# Sheet1.net
KiCad netlist of a schematic drawn in Altium Designer
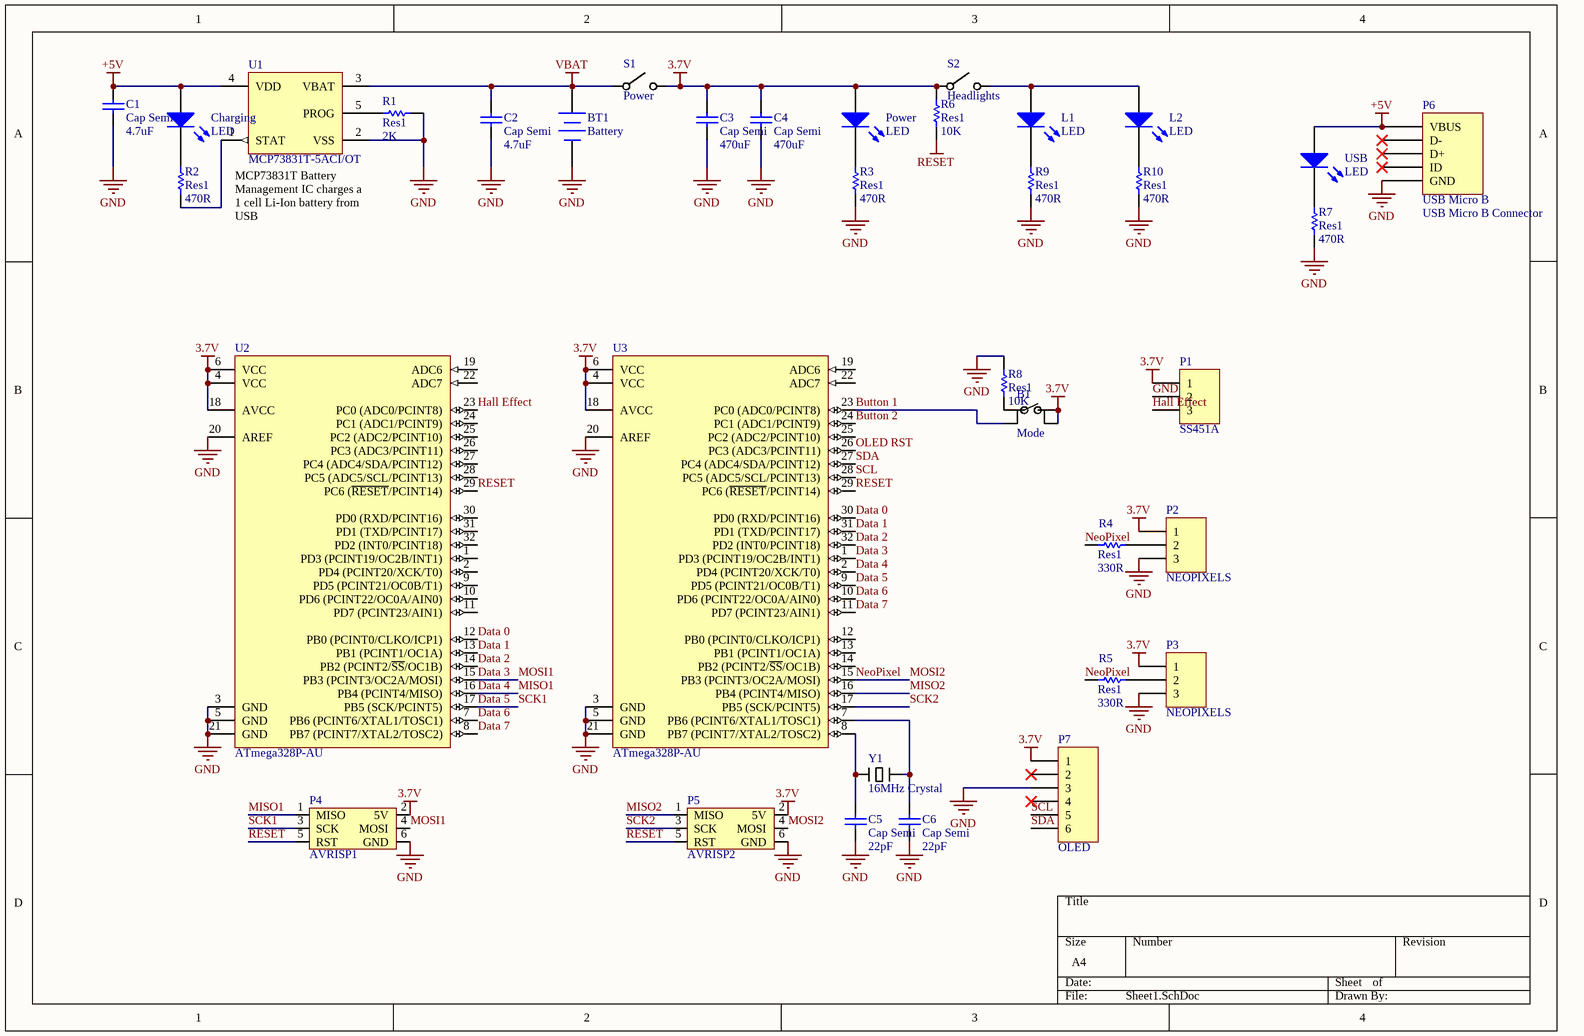
[diagram p0: Sheet1.SchDoc]

(export (version "E")
  (design (tool "Eeschema 10.0.6"))
  (components
    (comp (ref "B1")
      (value "Mode")
      (footprint "SPST-NO")
      (libsource (lib "WillsSchematicLibrary") (part "Switch"))
    )
    (comp (ref "BT1")
      (value "Battery")
      (footprint "BAT-2")
      (description "Multicell Battery")
      (fields (field (name "PUBLISHER") "Altium Limited"))
      (libsource (lib "Miscellaneous Devices") (part "Battery"))
    )
    (comp (ref "C1")
      (value "Cap Semi")
      (footprint "1608[0603]")
      (description "Capacitor (Semiconductor SIM Model)")
      (fields (field (name "ALTIUM_VALUE") "4.7uF") (field (name "PUBLISHER") "Altium Limited"))
      (libsource (lib "Miscellaneous Devices") (part "Cap Semi"))
    )
    (comp (ref "C2")
      (value "Cap Semi")
      (footprint "1608[0603]")
      (description "Capacitor (Semiconductor SIM Model)")
      (fields (field (name "ALTIUM_VALUE") "4.7uF") (field (name "PUBLISHER") "Altium Limited"))
      (libsource (lib "Miscellaneous Devices") (part "Cap Semi"))
    )
    (comp (ref "C3")
      (value "Cap Semi")
      (footprint "CAPAE9983X105M")
      (description "Capacitor (Semiconductor SIM Model)")
      (fields (field (name "ALTIUM_VALUE") "470uF") (field (name "PUBLISHER") "Altium Limited"))
      (libsource (lib "Miscellaneous Devices") (part "Cap Semi"))
    )
    (comp (ref "C4")
      (value "Cap Semi")
      (footprint "CAPAE9983X105M")
      (description "Capacitor (Semiconductor SIM Model)")
      (fields (field (name "ALTIUM_VALUE") "470uF") (field (name "PUBLISHER") "Altium Limited"))
      (libsource (lib "Miscellaneous Devices") (part "Cap Semi"))
    )
    (comp (ref "C5")
      (value "Cap Semi")
      (footprint "1608[0603]")
      (description "Capacitor (Semiconductor SIM Model)")
      (fields (field (name "ALTIUM_VALUE") "22pF") (field (name "PUBLISHER") "Altium Limited"))
      (libsource (lib "Miscellaneous Devices") (part "Cap Semi"))
    )
    (comp (ref "C6")
      (value "Cap Semi")
      (footprint "1608[0603]")
      (description "Capacitor (Semiconductor SIM Model)")
      (fields (field (name "ALTIUM_VALUE") "22pF") (field (name "PUBLISHER") "Altium Limited"))
      (libsource (lib "Miscellaneous Devices") (part "Cap Semi"))
    )
    (comp (ref "Charging")
      (value "LED")
      (footprint "LED0603")
      (description "Typical BLUE SiC LED")
      (fields (field (name "PUBLISHER") "Altium Limited"))
      (libsource (lib "Miscellaneous Devices") (part "LED3"))
    )
    (comp (ref "L1")
      (value "LED")
      (footprint "HDR1X2")
      (description "Typical BLUE SiC LED")
      (fields (field (name "PUBLISHER") "Altium Limited"))
      (libsource (lib "Miscellaneous Devices") (part "LED3"))
    )
    (comp (ref "L2")
      (value "LED")
      (footprint "HDR1X2")
      (description "Typical BLUE SiC LED")
      (fields (field (name "PUBLISHER") "Altium Limited"))
      (libsource (lib "Miscellaneous Devices") (part "LED3"))
    )
    (comp (ref "P1")
      (value "SS451A")
      (footprint "HDR1X3")
      (description "Header, 3-Pin")
      (fields (field (name "PUBLISHER") "Altium Limited"))
      (libsource (lib "Miscellaneous Connectors") (part "Header 3"))
    )
    (comp (ref "P2")
      (value "NEOPIXELS")
      (footprint "HDR1X3")
      (description "Header, 3-Pin")
      (fields (field (name "PUBLISHER") "Altium Limited"))
      (libsource (lib "Miscellaneous Connectors") (part "Header 3"))
    )
    (comp (ref "P3")
      (value "NEOPIXELS")
      (footprint "HDR1X3")
      (description "Header, 3-Pin")
      (fields (field (name "PUBLISHER") "Altium Limited"))
      (libsource (lib "Miscellaneous Connectors") (part "Header 3"))
    )
    (comp (ref "P4")
      (value "AVRISP1")
      (footprint "HDR2X3")
      (libsource (lib "WillsSchematicLibrary") (part "AVRISP"))
    )
    (comp (ref "P5")
      (value "AVRISP2")
      (footprint "HDR2X3")
      (libsource (lib "WillsSchematicLibrary") (part "AVRISP"))
    )
    (comp (ref "P6")
      (value "USB Micro B Connector")
      (footprint "USB Micro B Connector")
      (libsource (lib "WillsSchematicLibrary") (part "USB Micro B Connector"))
    )
    (comp (ref "P7")
      (value "OLED")
      (footprint "HDR1X6")
      (description "Header, 6-Pin")
      (fields (field (name "PUBLISHER") "Altium Limited"))
      (libsource (lib "Miscellaneous Connectors") (part "Header 6"))
    )
    (comp (ref "Power")
      (value "LED")
      (footprint "LED0603")
      (description "Typical BLUE SiC LED")
      (fields (field (name "PUBLISHER") "Altium Limited"))
      (libsource (lib "Miscellaneous Devices") (part "LED3"))
    )
    (comp (ref "R1")
      (value "Res1")
      (footprint "1608[0603]")
      (description "Resistor")
      (fields (field (name "ALTIUM_VALUE") "2K") (field (name "PUBLISHER") "Altium Limited"))
      (libsource (lib "Miscellaneous Devices") (part "Res1"))
    )
    (comp (ref "R2")
      (value "Res1")
      (footprint "1608[0603]")
      (description "Resistor")
      (fields (field (name "ALTIUM_VALUE") "470R") (field (name "PUBLISHER") "Altium Limited"))
      (libsource (lib "Miscellaneous Devices") (part "Res1"))
    )
    (comp (ref "R3")
      (value "Res1")
      (footprint "1608[0603]")
      (description "Resistor")
      (fields (field (name "ALTIUM_VALUE") "470R") (field (name "PUBLISHER") "Altium Limited"))
      (libsource (lib "Miscellaneous Devices") (part "Res1"))
    )
    (comp (ref "R4")
      (value "Res1")
      (footprint "1608[0603]")
      (description "Resistor")
      (fields (field (name "ALTIUM_VALUE") "330R") (field (name "PUBLISHER") "Altium Limited"))
      (libsource (lib "Miscellaneous Devices") (part "Res1"))
    )
    (comp (ref "R5")
      (value "Res1")
      (footprint "1608[0603]")
      (description "Resistor")
      (fields (field (name "ALTIUM_VALUE") "330R") (field (name "PUBLISHER") "Altium Limited"))
      (libsource (lib "Miscellaneous Devices") (part "Res1"))
    )
    (comp (ref "R6")
      (value "Res1")
      (footprint "1608[0603]")
      (description "Resistor")
      (fields (field (name "ALTIUM_VALUE") "10K") (field (name "PUBLISHER") "Altium Limited"))
      (libsource (lib "Miscellaneous Devices") (part "Res1"))
    )
    (comp (ref "R7")
      (value "Res1")
      (footprint "1608[0603]")
      (description "Resistor")
      (fields (field (name "ALTIUM_VALUE") "470R") (field (name "PUBLISHER") "Altium Limited"))
      (libsource (lib "Miscellaneous Devices") (part "Res1"))
    )
    (comp (ref "R8")
      (value "Res1")
      (footprint "1608[0603]")
      (description "Resistor")
      (fields (field (name "ALTIUM_VALUE") "10K") (field (name "PUBLISHER") "Altium Limited"))
      (libsource (lib "Miscellaneous Devices") (part "Res1"))
    )
    (comp (ref "R9")
      (value "Res1")
      (footprint "1608[0603]")
      (description "Resistor")
      (fields (field (name "ALTIUM_VALUE") "470R") (field (name "PUBLISHER") "Altium Limited"))
      (libsource (lib "Miscellaneous Devices") (part "Res1"))
    )
    (comp (ref "R10")
      (value "Res1")
      (footprint "1608[0603]")
      (description "Resistor")
      (fields (field (name "ALTIUM_VALUE") "470R") (field (name "PUBLISHER") "Altium Limited"))
      (libsource (lib "Miscellaneous Devices") (part "Res1"))
    )
    (comp (ref "S1")
      (value "Power")
      (footprint "Slide Switch 2.54mm")
      (libsource (lib "WillsSchematicLibrary") (part "Slide Switch"))
    )
    (comp (ref "S2")
      (value "Headlights")
      (footprint "Slide Switch 2.54mm")
      (libsource (lib "WillsSchematicLibrary") (part "Slide Switch"))
    )
    (comp (ref "U1")
      (value "MCP73831T-5ACI/OT")
      (footprint "SOT-23-OT5_N")
      (fields (field (name "MANUFACTURER") "Microchip"))
      (libsource (lib "Microchip Power Management Battery Management") (part "MCP73831T-5ACI/OT"))
    )
    (comp (ref "U2")
      (value "ATmega328P-AU")
      (footprint "32A_N")
      (libsource (lib "Atmel Microcontroller megaAVR") (part "ATmega328P-AU"))
    )
    (comp (ref "U3")
      (value "ATmega328P-AU")
      (footprint "32A_N")
      (libsource (lib "Atmel Microcontroller megaAVR") (part "ATmega328P-AU"))
    )
    (comp (ref "USB")
      (value "LED")
      (footprint "LED0603")
      (description "Typical BLUE SiC LED")
      (fields (field (name "PUBLISHER") "Altium Limited"))
      (libsource (lib "Miscellaneous Devices") (part "LED3"))
    )
    (comp (ref "Y1")
      (value "16MHz Crystal")
      (footprint "16MHz Clock")
      (libsource (lib "WillsSchematicLibrary") (part "16MHz Crystal"))
    )
  )
  (nets
    (net (code "1") (name "+5V") (class "Default")
      (node (ref "C1") (pin "2") (pinfunction "2_2") (pintype "passive"))
      (node (ref "Charging") (pin "1") (pinfunction "A_1") (pintype "passive"))
      (node (ref "P6") (pin "VBUS") (pinfunction "VBUS_VBUS") (pintype "passive"))
      (node (ref "U1") (pin "4") (pinfunction "VDD_4") (pintype "power_in"))
      (node (ref "USB") (pin "1") (pinfunction "A_1") (pintype "passive"))
    )
    (net (code "2") (name "/Button 1") (class "Default")
      (node (ref "B1") (pin "2") (pinfunction "2_2") (pintype "passive"))
      (node (ref "U3") (pin "23") (pinfunction "PC0_(ADC0/PCINT8)_23") (pintype "bidirectional"))
    )
    (net (code "3") (name "/Button 2") (class "Default")
      (node (ref "U3") (pin "24") (pinfunction "PC1_(ADC1/PCINT9)_24") (pintype "bidirectional"))
    )
    (net (code "4") (name "/Data 0") (class "Default")
      (node (ref "U2") (pin "12") (pinfunction "PB0_(PCINT0/CLKO/ICP1)_12") (pintype "bidirectional"))
      (node (ref "U3") (pin "30") (pinfunction "PD0_(RXD/PCINT16)_30") (pintype "bidirectional"))
    )
    (net (code "5") (name "/Data 1") (class "Default")
      (node (ref "U2") (pin "13") (pinfunction "PB1_(PCINT1/OC1A)_13") (pintype "bidirectional"))
      (node (ref "U3") (pin "31") (pinfunction "PD1_(TXD/PCINT17)_31") (pintype "bidirectional"))
    )
    (net (code "6") (name "/Data 2") (class "Default")
      (node (ref "U2") (pin "14") (pinfunction "PB2_(PCINT2/~{SS}/OC1B)_14") (pintype "bidirectional"))
      (node (ref "U3") (pin "32") (pinfunction "PD2_(INT0/PCINT18)_32") (pintype "bidirectional"))
    )
    (net (code "7") (name "/Data 3") (class "Default")
      (node (ref "P4") (pin "4") (pinfunction "MOSI_4") (pintype "passive"))
      (node (ref "U2") (pin "15") (pinfunction "PB3_(PCINT3/OC2A/MOSI)_15") (pintype "bidirectional"))
      (node (ref "U3") (pin "1") (pinfunction "PD3_(PCINT19/OC2B/INT1)_1") (pintype "bidirectional"))
    )
    (net (code "8") (name "/Data 4") (class "Default")
      (node (ref "P4") (pin "1") (pinfunction "MISO_1") (pintype "passive"))
      (node (ref "U2") (pin "16") (pinfunction "PB4_(PCINT4/MISO)_16") (pintype "bidirectional"))
      (node (ref "U3") (pin "2") (pinfunction "PD4_(PCINT20/XCK/T0)_2") (pintype "bidirectional"))
    )
    (net (code "9") (name "/Data 5") (class "Default")
      (node (ref "P4") (pin "3") (pinfunction "SCK_3") (pintype "passive"))
      (node (ref "U2") (pin "17") (pinfunction "PB5_(SCK/PCINT5)_17") (pintype "bidirectional"))
      (node (ref "U3") (pin "9") (pinfunction "PD5_(PCINT21/OC0B/T1)_9") (pintype "bidirectional"))
    )
    (net (code "10") (name "/Data 6") (class "Default")
      (node (ref "U2") (pin "7") (pinfunction "PB6_(PCINT6/XTAL1/TOSC1)_7") (pintype "bidirectional"))
      (node (ref "U3") (pin "10") (pinfunction "PD6_(PCINT22/OC0A/AIN0)_10") (pintype "bidirectional"))
    )
    (net (code "11") (name "/Data 7") (class "Default")
      (node (ref "U2") (pin "8") (pinfunction "PB7_(PCINT7/XTAL2/TOSC2)_8") (pintype "bidirectional"))
      (node (ref "U3") (pin "11") (pinfunction "PD7_(PCINT23/AIN1)_11") (pintype "bidirectional"))
    )
    (net (code "12") (name "/Hall Effect") (class "Default")
      (node (ref "P1") (pin "3") (pinfunction "3_3") (pintype "passive"))
      (node (ref "U2") (pin "23") (pinfunction "PC0_(ADC0/PCINT8)_23") (pintype "bidirectional"))
    )
    (net (code "13") (name "/MISO2") (class "Default")
      (node (ref "P5") (pin "1") (pinfunction "MISO_1") (pintype "passive"))
      (node (ref "U3") (pin "16") (pinfunction "PB4_(PCINT4/MISO)_16") (pintype "bidirectional"))
    )
    (net (code "14") (name "/MOSI2") (class "Default")
      (node (ref "P5") (pin "4") (pinfunction "MOSI_4") (pintype "passive"))
      (node (ref "R4") (pin "1") (pinfunction "1_1") (pintype "passive"))
      (node (ref "R5") (pin "1") (pinfunction "1_1") (pintype "passive"))
      (node (ref "U3") (pin "15") (pinfunction "PB3_(PCINT3/OC2A/MOSI)_15") (pintype "bidirectional"))
    )
    (net (code "15") (name "/OLED RST") (class "Default")
      (node (ref "U3") (pin "26") (pinfunction "PC3_(ADC3/PCINT11)_26") (pintype "bidirectional"))
    )
    (net (code "16") (name "/SCK2") (class "Default")
      (node (ref "P5") (pin "3") (pinfunction "SCK_3") (pintype "passive"))
      (node (ref "U3") (pin "17") (pinfunction "PB5_(SCK/PCINT5)_17") (pintype "bidirectional"))
    )
    (net (code "17") (name "/SCL") (class "Default")
      (node (ref "P7") (pin "5") (pinfunction "5_5") (pintype "passive"))
      (node (ref "U3") (pin "28") (pinfunction "PC5_(ADC5/SCL/PCINT13)_28") (pintype "bidirectional"))
    )
    (net (code "18") (name "/SDA") (class "Default")
      (node (ref "P7") (pin "6") (pinfunction "6_6") (pintype "passive"))
      (node (ref "U3") (pin "27") (pinfunction "PC4_(ADC4/SDA/PCINT12)_27") (pintype "bidirectional"))
    )
    (net (code "19") (name "3.7V") (class "Default")
      (node (ref "B1") (pin "3") (pinfunction "3_3") (pintype "passive"))
      (node (ref "B1") (pin "4") (pinfunction "4_4") (pintype "passive"))
      (node (ref "C3") (pin "2") (pinfunction "2_2") (pintype "passive"))
      (node (ref "C4") (pin "2") (pinfunction "2_2") (pintype "passive"))
      (node (ref "P1") (pin "1") (pinfunction "1_1") (pintype "passive"))
      (node (ref "P2") (pin "1") (pinfunction "1_1") (pintype "passive"))
      (node (ref "P3") (pin "1") (pinfunction "1_1") (pintype "passive"))
      (node (ref "P4") (pin "2") (pinfunction "5V_2") (pintype "passive"))
      (node (ref "P5") (pin "2") (pinfunction "5V_2") (pintype "passive"))
      (node (ref "P7") (pin "1") (pinfunction "1_1") (pintype "passive"))
      (node (ref "Power") (pin "1") (pinfunction "A_1") (pintype "passive"))
      (node (ref "R6") (pin "1") (pinfunction "1_1") (pintype "passive"))
      (node (ref "S1") (pin "2") (pinfunction "2_2") (pintype "passive"))
      (node (ref "S2") (pin "1") (pinfunction "1_1") (pintype "passive"))
      (node (ref "U2") (pin "18") (pinfunction "AVCC_18") (pintype "power_in"))
      (node (ref "U2") (pin "4") (pinfunction "VCC_4") (pintype "power_in"))
      (node (ref "U2") (pin "6") (pinfunction "VCC_6") (pintype "power_in"))
      (node (ref "U3") (pin "18") (pinfunction "AVCC_18") (pintype "power_in"))
      (node (ref "U3") (pin "4") (pinfunction "VCC_4") (pintype "power_in"))
      (node (ref "U3") (pin "6") (pinfunction "VCC_6") (pintype "power_in"))
    )
    (net (code "20") (name "GND") (class "Default")
      (node (ref "BT1") (pin "2") (pinfunction "-_2") (pintype "passive"))
      (node (ref "C1") (pin "1") (pinfunction "1_1") (pintype "passive"))
      (node (ref "C2") (pin "1") (pinfunction "1_1") (pintype "passive"))
      (node (ref "C3") (pin "1") (pinfunction "1_1") (pintype "passive"))
      (node (ref "C4") (pin "1") (pinfunction "1_1") (pintype "passive"))
      (node (ref "C5") (pin "1") (pinfunction "1_1") (pintype "passive"))
      (node (ref "C6") (pin "1") (pinfunction "1_1") (pintype "passive"))
      (node (ref "P1") (pin "2") (pinfunction "2_2") (pintype "passive"))
      (node (ref "P2") (pin "3") (pinfunction "3_3") (pintype "passive"))
      (node (ref "P3") (pin "3") (pinfunction "3_3") (pintype "passive"))
      (node (ref "P4") (pin "6") (pinfunction "GND_6") (pintype "passive"))
      (node (ref "P5") (pin "6") (pinfunction "GND_6") (pintype "passive"))
      (node (ref "P6") (pin "GND") (pinfunction "GND_GND") (pintype "passive"))
      (node (ref "P7") (pin "3") (pinfunction "3_3") (pintype "passive"))
      (node (ref "R1") (pin "1") (pinfunction "1_1") (pintype "passive"))
      (node (ref "R10") (pin "1") (pinfunction "1_1") (pintype "passive"))
      (node (ref "R3") (pin "1") (pinfunction "1_1") (pintype "passive"))
      (node (ref "R7") (pin "1") (pinfunction "1_1") (pintype "passive"))
      (node (ref "R8") (pin "1") (pinfunction "1_1") (pintype "passive"))
      (node (ref "R9") (pin "1") (pinfunction "1_1") (pintype "passive"))
      (node (ref "U1") (pin "2") (pinfunction "VSS_2") (pintype "power_in"))
      (node (ref "U2") (pin "20") (pinfunction "AREF_20") (pintype "passive"))
      (node (ref "U2") (pin "21") (pinfunction "GND_21") (pintype "power_in"))
      (node (ref "U2") (pin "3") (pinfunction "GND_3") (pintype "power_in"))
      (node (ref "U2") (pin "5") (pinfunction "GND_5") (pintype "power_in"))
      (node (ref "U3") (pin "20") (pinfunction "AREF_20") (pintype "passive"))
      (node (ref "U3") (pin "21") (pinfunction "GND_21") (pintype "power_in"))
      (node (ref "U3") (pin "3") (pinfunction "GND_3") (pintype "power_in"))
      (node (ref "U3") (pin "5") (pinfunction "GND_5") (pintype "power_in"))
    )
    (net (code "21") (name "Net-(B1-Pad1)") (class "Default")
      (node (ref "B1") (pin "1") (pinfunction "1_1") (pintype "passive"))
      (node (ref "R8") (pin "2") (pinfunction "2_2") (pintype "passive"))
    )
    (net (code "22") (name "Net-(Charging-K)") (class "Default")
      (node (ref "Charging") (pin "2") (pinfunction "K_2") (pintype "passive"))
      (node (ref "R2") (pin "2") (pinfunction "2_2") (pintype "passive"))
    )
    (net (code "23") (name "Net-(L1-A)") (class "Default")
      (node (ref "L1") (pin "1") (pinfunction "A_1") (pintype "passive"))
      (node (ref "L2") (pin "1") (pinfunction "A_1") (pintype "passive"))
      (node (ref "S2") (pin "2") (pinfunction "2_2") (pintype "passive"))
    )
    (net (code "24") (name "Net-(L1-K)") (class "Default")
      (node (ref "L1") (pin "2") (pinfunction "K_2") (pintype "passive"))
      (node (ref "R9") (pin "2") (pinfunction "2_2") (pintype "passive"))
    )
    (net (code "25") (name "Net-(L2-K)") (class "Default")
      (node (ref "L2") (pin "2") (pinfunction "K_2") (pintype "passive"))
      (node (ref "R10") (pin "2") (pinfunction "2_2") (pintype "passive"))
    )
    (net (code "26") (name "Net-(P2-Pad2)") (class "Default")
      (node (ref "P2") (pin "2") (pinfunction "2_2") (pintype "passive"))
      (node (ref "R4") (pin "2") (pinfunction "2_2") (pintype "passive"))
    )
    (net (code "27") (name "Net-(P3-Pad2)") (class "Default")
      (node (ref "P3") (pin "2") (pinfunction "2_2") (pintype "passive"))
      (node (ref "R5") (pin "2") (pinfunction "2_2") (pintype "passive"))
    )
    (net (code "28") (name "Net-(Power-K)") (class "Default")
      (node (ref "Power") (pin "2") (pinfunction "K_2") (pintype "passive"))
      (node (ref "R3") (pin "2") (pinfunction "2_2") (pintype "passive"))
    )
    (net (code "29") (name "Net-(U1-PROG)") (class "Default")
      (node (ref "R1") (pin "2") (pinfunction "2_2") (pintype "passive"))
      (node (ref "U1") (pin "5") (pinfunction "PROG_5") (pintype "passive"))
    )
    (net (code "30") (name "Net-(U1-STAT)") (class "Default")
      (node (ref "R2") (pin "1") (pinfunction "1_1") (pintype "passive"))
      (node (ref "U1") (pin "1") (pinfunction "STAT_1") (pintype "output"))
    )
    (net (code "31") (name "Net-(U3-PB6_(PCINT6{slash}XTAL1{slash}TOSC1))") (class "Default")
      (node (ref "C6") (pin "2") (pinfunction "2_2") (pintype "passive"))
      (node (ref "U3") (pin "7") (pinfunction "PB6_(PCINT6/XTAL1/TOSC1)_7") (pintype "bidirectional"))
      (node (ref "Y1") (pin "2") (pinfunction "2_2") (pintype "passive"))
    )
    (net (code "32") (name "Net-(U3-PB7_(PCINT7{slash}XTAL2{slash}TOSC2))") (class "Default")
      (node (ref "C5") (pin "2") (pinfunction "2_2") (pintype "passive"))
      (node (ref "U3") (pin "8") (pinfunction "PB7_(PCINT7/XTAL2/TOSC2)_8") (pintype "bidirectional"))
      (node (ref "Y1") (pin "1") (pinfunction "1_1") (pintype "passive"))
    )
    (net (code "33") (name "Net-(USB-K)") (class "Default")
      (node (ref "R7") (pin "2") (pinfunction "2_2") (pintype "passive"))
      (node (ref "USB") (pin "2") (pinfunction "K_2") (pintype "passive"))
    )
    (net (code "34") (name "RESET") (class "Default")
      (node (ref "P4") (pin "5") (pinfunction "RST_5") (pintype "passive"))
      (node (ref "P5") (pin "5") (pinfunction "RST_5") (pintype "passive"))
      (node (ref "R6") (pin "2") (pinfunction "2_2") (pintype "passive"))
      (node (ref "U2") (pin "29") (pinfunction "PC6_(~{RESET}/PCINT14)_29") (pintype "bidirectional"))
      (node (ref "U3") (pin "29") (pinfunction "PC6_(~{RESET}/PCINT14)_29") (pintype "bidirectional"))
    )
    (net (code "35") (name "VBAT") (class "Default")
      (node (ref "BT1") (pin "1") (pinfunction "+_1") (pintype "passive"))
      (node (ref "C2") (pin "2") (pinfunction "2_2") (pintype "passive"))
      (node (ref "S1") (pin "1") (pinfunction "1_1") (pintype "passive"))
      (node (ref "U1") (pin "3") (pinfunction "VBAT_3") (pintype "power_in"))
    )
    (net (code "36") (name "unconnected-(P6-PadD+)") (class "Default")
      (node (ref "P6") (pin "D+") (pinfunction "D+_D+") (pintype "passive+no_connect"))
    )
    (net (code "37") (name "unconnected-(P6-PadD-)") (class "Default")
      (node (ref "P6") (pin "D-") (pinfunction "D-_D-") (pintype "passive+no_connect"))
    )
    (net (code "38") (name "unconnected-(P6-PadID)") (class "Default")
      (node (ref "P6") (pin "ID") (pinfunction "ID_ID") (pintype "passive+no_connect"))
    )
    (net (code "39") (name "unconnected-(P7-Pad2)") (class "Default")
      (node (ref "P7") (pin "2") (pinfunction "2_2") (pintype "passive+no_connect"))
    )
    (net (code "40") (name "unconnected-(P7-Pad4)") (class "Default")
      (node (ref "P7") (pin "4") (pinfunction "4_4") (pintype "passive+no_connect"))
    )
    (net (code "41") (name "unconnected-(U2-ADC6-Pad19)") (class "Default")
      (node (ref "U2") (pin "19") (pinfunction "ADC6_19") (pintype "input"))
    )
    (net (code "42") (name "unconnected-(U2-ADC7-Pad22)") (class "Default")
      (node (ref "U2") (pin "22") (pinfunction "ADC7_22") (pintype "input"))
    )
    (net (code "43") (name "unconnected-(U2-PC1_(ADC1{slash}PCINT9)-Pad24)") (class "Default")
      (node (ref "U2") (pin "24") (pinfunction "PC1_(ADC1/PCINT9)_24") (pintype "bidirectional"))
    )
    (net (code "44") (name "unconnected-(U2-PC2_(ADC2{slash}PCINT10)-Pad25)") (class "Default")
      (node (ref "U2") (pin "25") (pinfunction "PC2_(ADC2/PCINT10)_25") (pintype "bidirectional"))
    )
    (net (code "45") (name "unconnected-(U2-PC3_(ADC3{slash}PCINT11)-Pad26)") (class "Default")
      (node (ref "U2") (pin "26") (pinfunction "PC3_(ADC3/PCINT11)_26") (pintype "bidirectional"))
    )
    (net (code "46") (name "unconnected-(U2-PC4_(ADC4{slash}SDA{slash}PCINT12)-Pad27)") (class "Default")
      (node (ref "U2") (pin "27") (pinfunction "PC4_(ADC4/SDA/PCINT12)_27") (pintype "bidirectional"))
    )
    (net (code "47") (name "unconnected-(U2-PC5_(ADC5{slash}SCL{slash}PCINT13)-Pad28)") (class "Default")
      (node (ref "U2") (pin "28") (pinfunction "PC5_(ADC5/SCL/PCINT13)_28") (pintype "bidirectional"))
    )
    (net (code "48") (name "unconnected-(U2-PD0_(RXD{slash}PCINT16)-Pad30)") (class "Default")
      (node (ref "U2") (pin "30") (pinfunction "PD0_(RXD/PCINT16)_30") (pintype "bidirectional"))
    )
    (net (code "49") (name "unconnected-(U2-PD1_(TXD{slash}PCINT17)-Pad31)") (class "Default")
      (node (ref "U2") (pin "31") (pinfunction "PD1_(TXD/PCINT17)_31") (pintype "bidirectional"))
    )
    (net (code "50") (name "unconnected-(U2-PD2_(INT0{slash}PCINT18)-Pad32)") (class "Default")
      (node (ref "U2") (pin "32") (pinfunction "PD2_(INT0/PCINT18)_32") (pintype "bidirectional"))
    )
    (net (code "51") (name "unconnected-(U2-PD3_(PCINT19{slash}OC2B{slash}INT1)-Pad1)") (class "Default")
      (node (ref "U2") (pin "1") (pinfunction "PD3_(PCINT19/OC2B/INT1)_1") (pintype "bidirectional"))
    )
    (net (code "52") (name "unconnected-(U2-PD4_(PCINT20{slash}XCK{slash}T0)-Pad2)") (class "Default")
      (node (ref "U2") (pin "2") (pinfunction "PD4_(PCINT20/XCK/T0)_2") (pintype "bidirectional"))
    )
    (net (code "53") (name "unconnected-(U2-PD5_(PCINT21{slash}OC0B{slash}T1)-Pad9)") (class "Default")
      (node (ref "U2") (pin "9") (pinfunction "PD5_(PCINT21/OC0B/T1)_9") (pintype "bidirectional"))
    )
    (net (code "54") (name "unconnected-(U2-PD6_(PCINT22{slash}OC0A{slash}AIN0)-Pad10)") (class "Default")
      (node (ref "U2") (pin "10") (pinfunction "PD6_(PCINT22/OC0A/AIN0)_10") (pintype "bidirectional"))
    )
    (net (code "55") (name "unconnected-(U2-PD7_(PCINT23{slash}AIN1)-Pad11)") (class "Default")
      (node (ref "U2") (pin "11") (pinfunction "PD7_(PCINT23/AIN1)_11") (pintype "bidirectional"))
    )
    (net (code "56") (name "unconnected-(U3-ADC6-Pad19)") (class "Default")
      (node (ref "U3") (pin "19") (pinfunction "ADC6_19") (pintype "input"))
    )
    (net (code "57") (name "unconnected-(U3-ADC7-Pad22)") (class "Default")
      (node (ref "U3") (pin "22") (pinfunction "ADC7_22") (pintype "input"))
    )
    (net (code "58") (name "unconnected-(U3-PB0_(PCINT0{slash}CLKO{slash}ICP1)-Pad12)") (class "Default")
      (node (ref "U3") (pin "12") (pinfunction "PB0_(PCINT0/CLKO/ICP1)_12") (pintype "bidirectional"))
    )
    (net (code "59") (name "unconnected-(U3-PB1_(PCINT1{slash}OC1A)-Pad13)") (class "Default")
      (node (ref "U3") (pin "13") (pinfunction "PB1_(PCINT1/OC1A)_13") (pintype "bidirectional"))
    )
    (net (code "60") (name "unconnected-(U3-PB2_(PCINT2{slash}~{SS}{slash}OC1B)-Pad14)") (class "Default")
      (node (ref "U3") (pin "14") (pinfunction "PB2_(PCINT2/~{SS}/OC1B)_14") (pintype "bidirectional"))
    )
    (net (code "61") (name "unconnected-(U3-PC2_(ADC2{slash}PCINT10)-Pad25)") (class "Default")
      (node (ref "U3") (pin "25") (pinfunction "PC2_(ADC2/PCINT10)_25") (pintype "bidirectional"))
    )
  )
)
